# powermeter_buttons_and_leds.net
KiCad netlist of a schematic drawn in Altium Designer
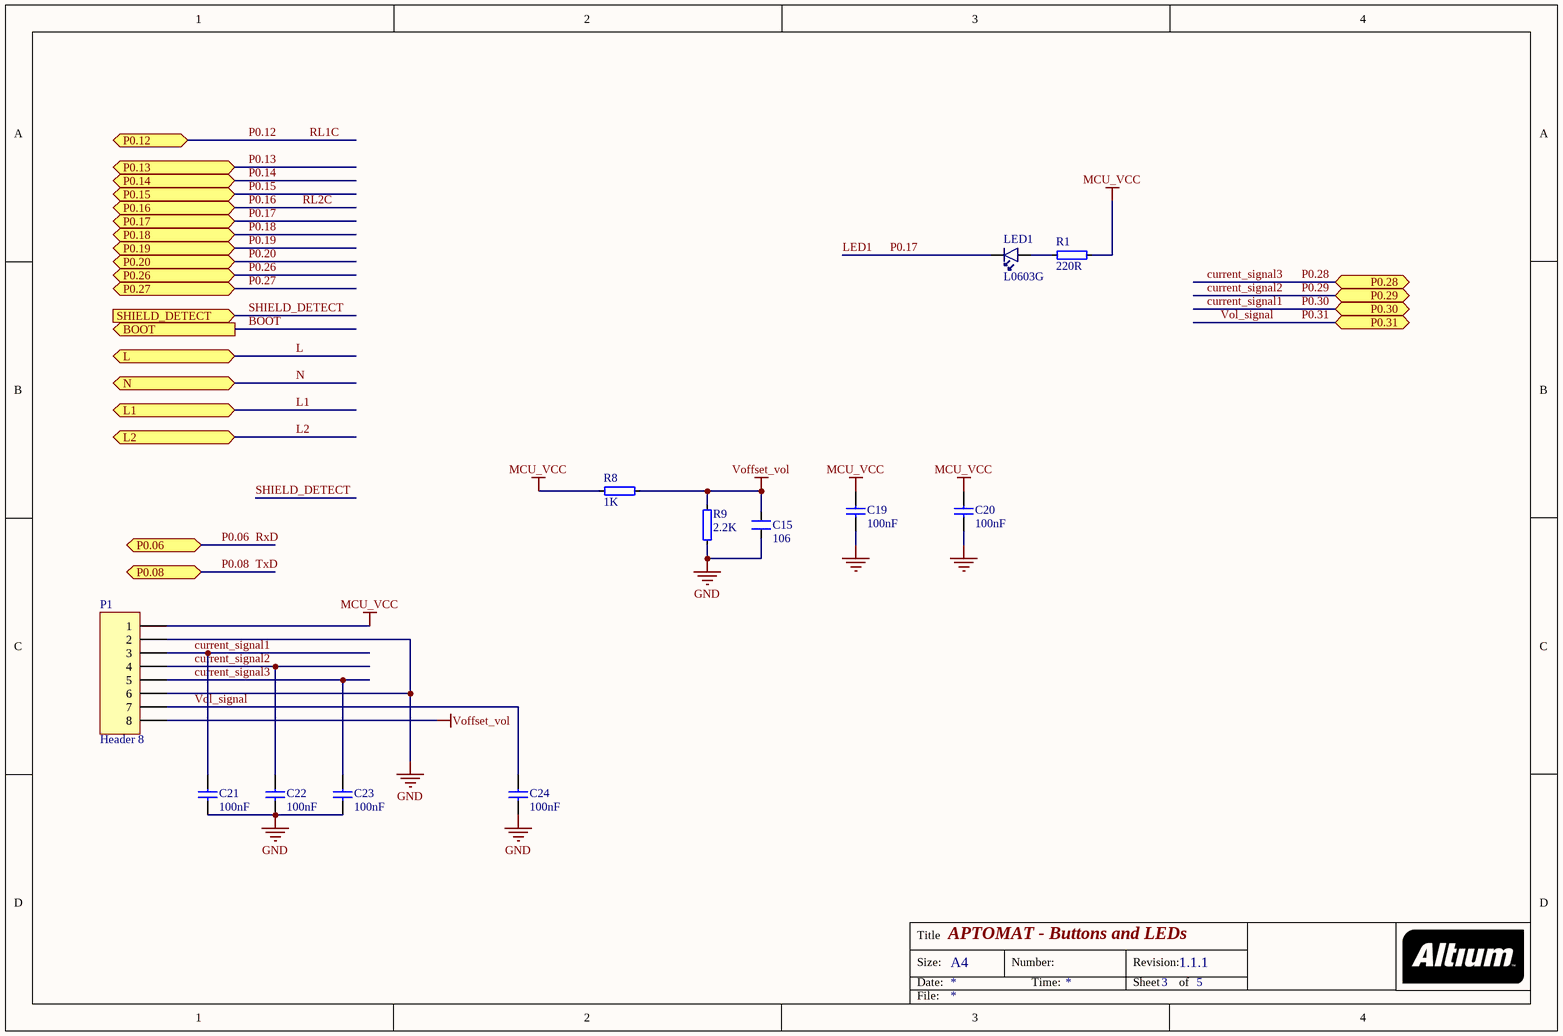
[diagram p0: powermeter_buttons_and_leds.SchDoc]

(export (version "E")
  (design (tool "Eeschema 10.0.6"))
  (components
    (comp (ref "C15")
      (value "106")
      (footprint "0805_HV")
      (description "Cap SMD")
      (libsource (lib "hatcatbietbay") (part "CM"))
    )
    (comp (ref "C19")
      (value "100nF")
      (footprint "0805_HV")
      (description "Capacitor, X7R, ±10%")
      (fields (field (name "PART NUMBER") "C0402-100n") (field (name "PUBLISHER") "Nordic Semiconductor"))
      (libsource (lib "Nordic Passive DB") (part "CAP"))
    )
    (comp (ref "C20")
      (value "100nF")
      (footprint "0805_HV")
      (description "Capacitor, X7R, ±10%")
      (fields (field (name "PART NUMBER") "C0402-100n") (field (name "PUBLISHER") "Nordic Semiconductor"))
      (libsource (lib "Nordic Passive DB") (part "CAP"))
    )
    (comp (ref "C21")
      (value "100nF")
      (footprint "0805_HV")
      (description "Capacitor, X7R, ±10%")
      (fields (field (name "PART NUMBER") "C0402-100n") (field (name "PUBLISHER") "Nordic Semiconductor"))
      (libsource (lib "Nordic Passive DB") (part "CAP"))
    )
    (comp (ref "C22")
      (value "100nF")
      (footprint "0805_HV")
      (description "Capacitor, X7R, ±10%")
      (fields (field (name "PART NUMBER") "C0402-100n") (field (name "PUBLISHER") "Nordic Semiconductor"))
      (libsource (lib "Nordic Passive DB") (part "CAP"))
    )
    (comp (ref "C23")
      (value "100nF")
      (footprint "0805_HV")
      (description "Capacitor, X7R, ±10%")
      (fields (field (name "PART NUMBER") "C0402-100n") (field (name "PUBLISHER") "Nordic Semiconductor"))
      (libsource (lib "Nordic Passive DB") (part "CAP"))
    )
    (comp (ref "C24")
      (value "100nF")
      (footprint "0805_HV")
      (description "Capacitor, X7R, ±10%")
      (fields (field (name "PART NUMBER") "C0402-100n") (field (name "PUBLISHER") "Nordic Semiconductor"))
      (libsource (lib "Nordic Passive DB") (part "CAP"))
    )
    (comp (ref "LED1")
      (value "L0603G")
      (footprint "LED_0603_G")
      (description "LED SMARTLED GREEN 570NM 0603")
      (fields
        (field (name "PART NUMBER") "LG L29K Smartled Green")
        (field (name "MANUFACTURER") "Multicomp")
        (field (name "PUBLISHER") "Nordic Semiconductor")
      )
      (libsource (lib "Nordic Discrete DB") (part "D{colon}LED"))
    )
    (comp (ref "P1")
      (value "Header 8")
      (footprint "CON6_1.5D")
      (description "Header, 8-Pin")
      (fields (field (name "PUBLISHER") "Altium Limited"))
      (libsource (lib "Miscellaneous Connectors") (part "Header 8"))
    )
    (comp (ref "R1")
      (value "220R")
      (footprint "0603")
      (description "Resistor, ±1%, 0.063W")
      (fields (field (name "PART NUMBER") "R0402-220") (field (name "PUBLISHER") "Nordic Semiconductor"))
      (libsource (lib "Nordic Passive DB") (part "RES_1"))
    )
    (comp (ref "R8")
      (value "1K")
      (footprint "0805_HV")
      (description "Resistor, ±1%, 0.063W")
      (fields (field (name "PART NUMBER") "R0402-100k") (field (name "PUBLISHER") "Nordic Semiconductor"))
      (libsource (lib "Nordic Passive DB") (part "RES_1"))
    )
    (comp (ref "R9")
      (value "2.2K")
      (footprint "0805_HV")
      (description "Resistor, ±1%, 0.063W")
      (fields (field (name "PART NUMBER") "R0402-100k") (field (name "PUBLISHER") "Nordic Semiconductor"))
      (libsource (lib "Nordic Passive DB") (part "RES_1"))
    )
  )
  (nets
    (net (code "5") (name "/LED1") (class "Default")
      (node (ref "LED1") (pin "1") (pinfunction "C_1") (pintype "passive"))
    )
    (net (code "19") (name "/P0.28") (class "Default")
      (node (ref "C23") (pin "2") (pinfunction "2_2") (pintype "passive"))
      (node (ref "P1") (pin "5") (pinfunction "5_5") (pintype "passive"))
    )
    (net (code "20") (name "/P0.29") (class "Default")
      (node (ref "C22") (pin "2") (pinfunction "2_2") (pintype "passive"))
      (node (ref "P1") (pin "4") (pinfunction "4_4") (pintype "passive"))
    )
    (net (code "21") (name "/P0.30") (class "Default")
      (node (ref "C21") (pin "2") (pinfunction "2_2") (pintype "passive"))
      (node (ref "P1") (pin "3") (pinfunction "3_3") (pintype "passive"))
    )
    (net (code "22") (name "/P0.31") (class "Default")
      (node (ref "C24") (pin "2") (pinfunction "2_2") (pintype "passive"))
      (node (ref "P1") (pin "7") (pinfunction "7_7") (pintype "passive"))
    )
    (net (code "24") (name "GND") (class "Default")
      (node (ref "C15") (pin "1") (pinfunction "1_1") (pintype "passive"))
      (node (ref "C19") (pin "1") (pinfunction "1_1") (pintype "passive"))
      (node (ref "C20") (pin "1") (pinfunction "1_1") (pintype "passive"))
      (node (ref "C21") (pin "1") (pinfunction "1_1") (pintype "passive"))
      (node (ref "C22") (pin "1") (pinfunction "1_1") (pintype "passive"))
      (node (ref "C23") (pin "1") (pinfunction "1_1") (pintype "passive"))
      (node (ref "C24") (pin "1") (pinfunction "1_1") (pintype "passive"))
      (node (ref "P1") (pin "2") (pinfunction "2_2") (pintype "passive"))
      (node (ref "P1") (pin "6") (pinfunction "6_6") (pintype "passive"))
      (node (ref "R9") (pin "2") (pinfunction "2_2") (pintype "passive"))
    )
    (net (code "25") (name "MCU_VCC") (class "Default")
      (node (ref "C19") (pin "2") (pinfunction "2_2") (pintype "passive"))
      (node (ref "C20") (pin "2") (pinfunction "2_2") (pintype "passive"))
      (node (ref "P1") (pin "1") (pinfunction "1_1") (pintype "passive"))
      (node (ref "R1") (pin "2") (pinfunction "2_2") (pintype "passive"))
      (node (ref "R8") (pin "2") (pinfunction "2_2") (pintype "passive"))
    )
    (net (code "26") (name "Net-(LED1-A)") (class "Default")
      (node (ref "LED1") (pin "2") (pinfunction "A_2") (pintype "passive"))
      (node (ref "R1") (pin "1") (pinfunction "1_1") (pintype "passive"))
    )
    (net (code "27") (name "Voffset_vol") (class "Default")
      (node (ref "C15") (pin "2") (pinfunction "2_2") (pintype "passive"))
      (node (ref "P1") (pin "8") (pinfunction "8_8") (pintype "passive"))
      (node (ref "R8") (pin "1") (pinfunction "1_1") (pintype "passive"))
      (node (ref "R9") (pin "1") (pinfunction "1_1") (pintype "passive"))
    )
  )
)
